# rrcmd.net
KiCad netlist of a schematic drawn in EAGLE
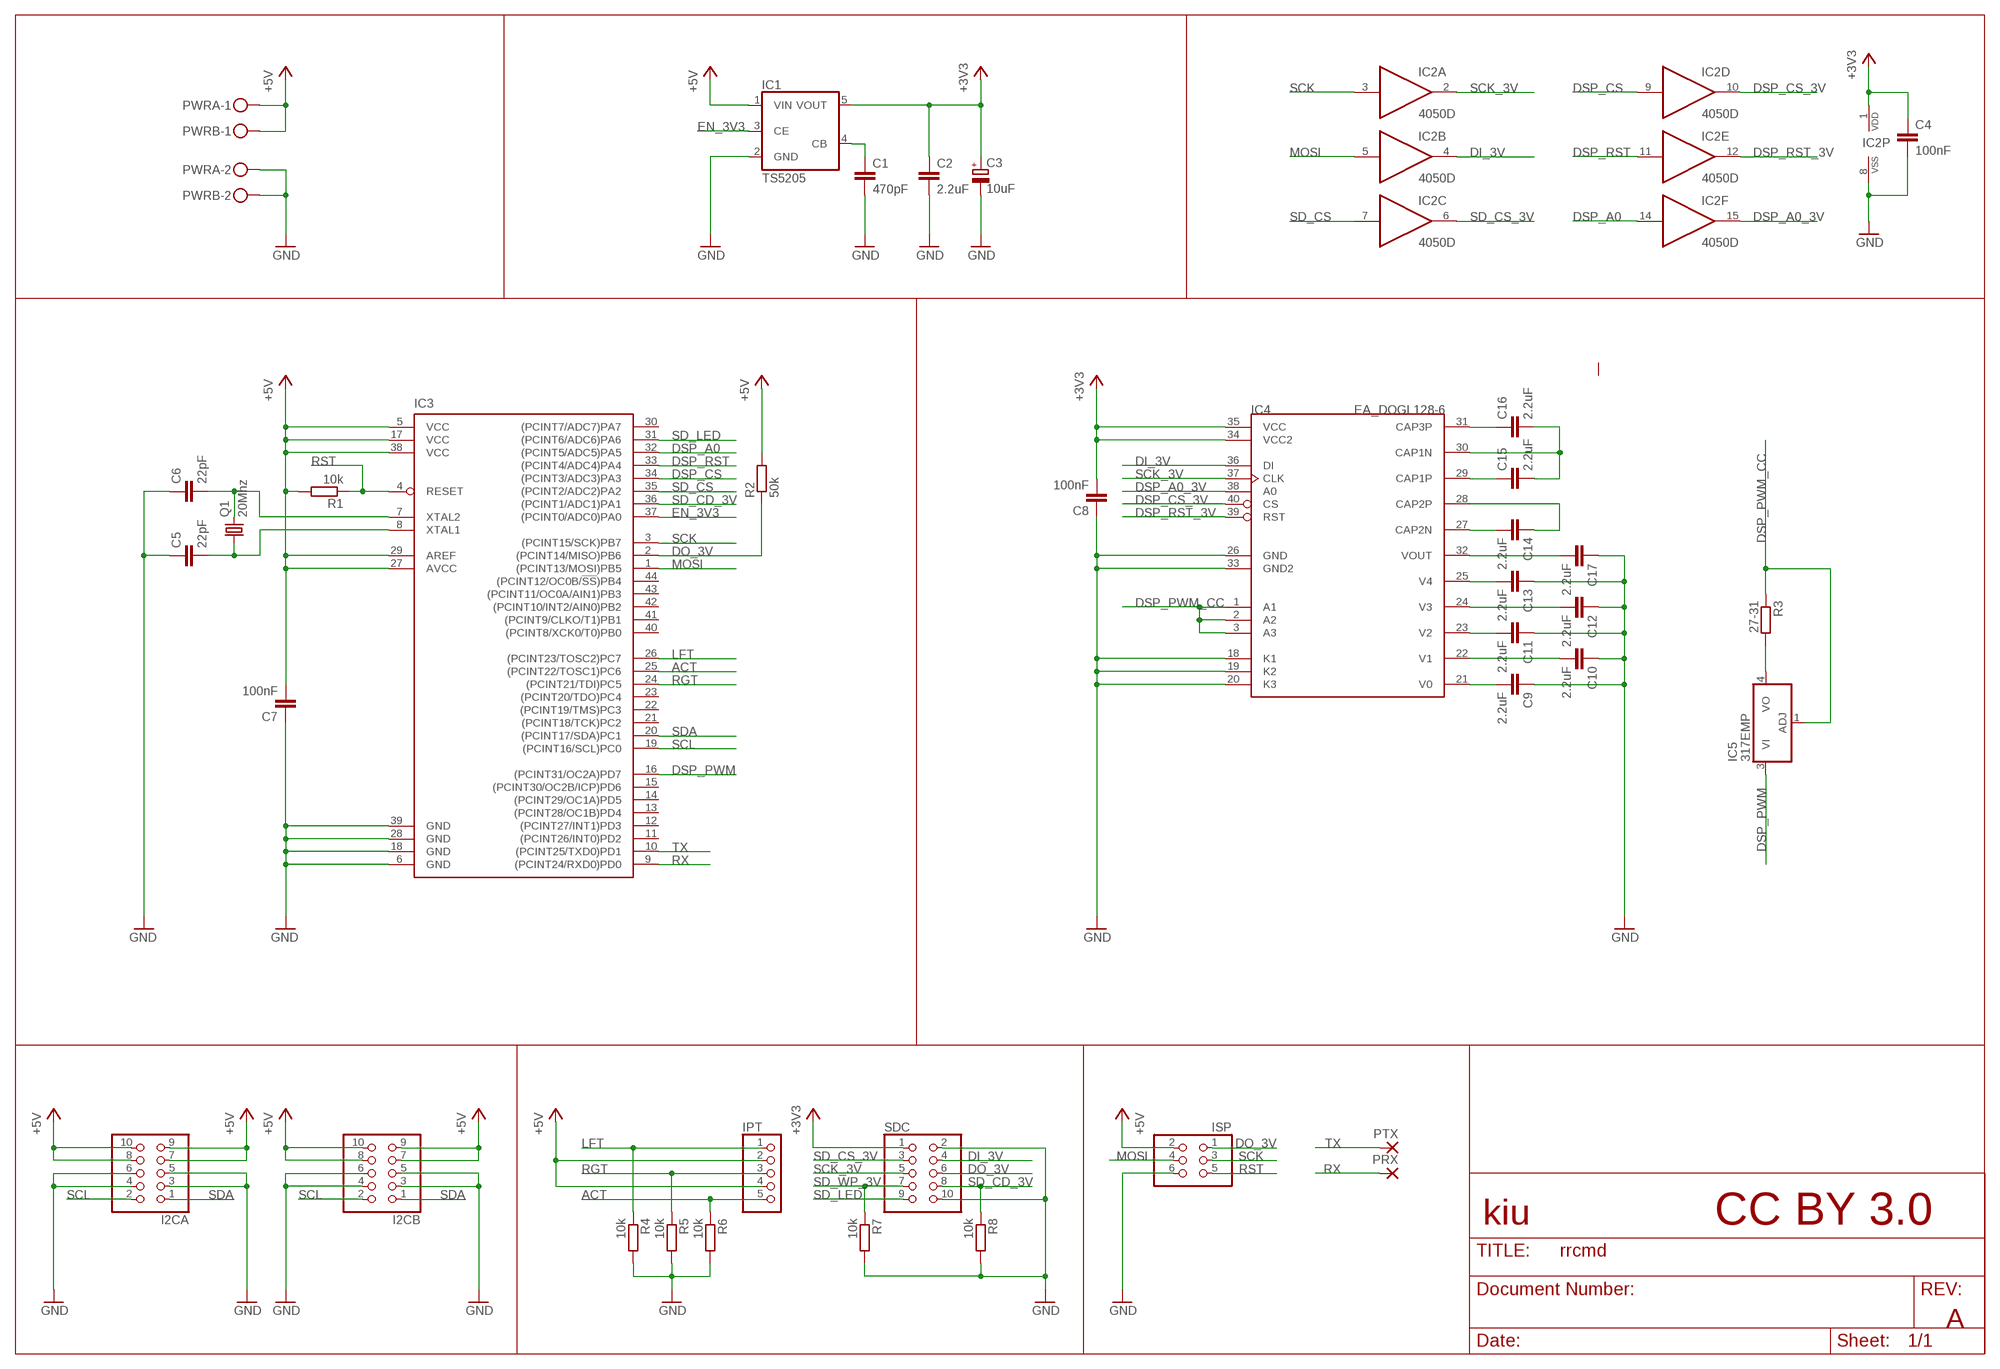
[diagram p0: schematic, sheet 1]

(export (version "E")
  (design (tool "Eeschema 10.0.6"))
  (components
    (comp (ref "C1")
      (value "470pF")
      (footprint "eagle-import:C0805")
      (libsource (lib "eagle-import") (part "C-EUC0805"))
    )
    (comp (ref "C2")
      (value "2.2uF")
      (footprint "eagle-import:C0805")
      (libsource (lib "eagle-import") (part "C-EUC0805"))
    )
    (comp (ref "C3")
      (value "10uF")
      (footprint "eagle-import:CT3216")
      (libsource (lib "eagle-import") (part "CPOL-EUCT3216"))
    )
    (comp (ref "C4")
      (value "100nF")
      (footprint "eagle-import:C0805")
      (libsource (lib "eagle-import") (part "C-EUC0805"))
    )
    (comp (ref "C5")
      (value "22pF")
      (footprint "eagle-import:C0805")
      (libsource (lib "eagle-import") (part "C-EUC0805"))
    )
    (comp (ref "C6")
      (value "22pF")
      (footprint "eagle-import:C0805")
      (libsource (lib "eagle-import") (part "C-EUC0805"))
    )
    (comp (ref "C7")
      (value "100nF")
      (footprint "eagle-import:C0805")
      (libsource (lib "eagle-import") (part "C-EUC0805"))
    )
    (comp (ref "C8")
      (value "100nF")
      (footprint "eagle-import:C0805")
      (libsource (lib "eagle-import") (part "C-EUC0805"))
    )
    (comp (ref "C9")
      (value "2.2uF")
      (footprint "eagle-import:C0805")
      (libsource (lib "eagle-import") (part "C-EUC0805"))
    )
    (comp (ref "C10")
      (value "2.2uF")
      (footprint "eagle-import:C0805")
      (libsource (lib "eagle-import") (part "C-EUC0805"))
    )
    (comp (ref "C11")
      (value "2.2uF")
      (footprint "eagle-import:C0805")
      (libsource (lib "eagle-import") (part "C-EUC0805"))
    )
    (comp (ref "C12")
      (value "2.2uF")
      (footprint "eagle-import:C0805")
      (libsource (lib "eagle-import") (part "C-EUC0805"))
    )
    (comp (ref "C13")
      (value "2.2uF")
      (footprint "eagle-import:C0805")
      (libsource (lib "eagle-import") (part "C-EUC0805"))
    )
    (comp (ref "C14")
      (value "2.2uF")
      (footprint "eagle-import:C0805")
      (libsource (lib "eagle-import") (part "C-EUC0805"))
    )
    (comp (ref "C15")
      (value "2.2uF")
      (footprint "eagle-import:C0805")
      (libsource (lib "eagle-import") (part "C-EUC0805"))
    )
    (comp (ref "C16")
      (value "2.2uF")
      (footprint "eagle-import:C0805")
      (libsource (lib "eagle-import") (part "C-EUC0805"))
    )
    (comp (ref "C17")
      (value "2.2uF")
      (footprint "eagle-import:C0805")
      (libsource (lib "eagle-import") (part "C-EUC0805"))
    )
    (comp (ref "I2CA")
      (value "PINHD-2X5")
      (footprint "eagle-import:2X05")
      (libsource (lib "eagle-import") (part "PINHD-2X5"))
    )
    (comp (ref "I2CB")
      (value "PINHD-2X5")
      (footprint "eagle-import:2X05")
      (libsource (lib "eagle-import") (part "PINHD-2X5"))
    )
    (comp (ref "IC1")
      (value "TS5205")
      (footprint "eagle-import:SOT25")
      (libsource (lib "eagle-import") (part "TS5205"))
    )
    (comp (ref "IC2")
      (value "4050D")
      (footprint "eagle-import:SO16")
      (libsource (lib "eagle-import") (part "4050D"))
    )
    (comp (ref "IC3")
      (value "ATMEGA644A")
      (footprint "eagle-import:TQFP44")
      (fields (field (name "MPN") "ATMEGA644PV-10AU"))
      (libsource (lib "eagle-import") (part "ATMEGA644A"))
    )
    (comp (ref "IC4")
      (value "EA_DOGL128-6")
      (footprint "eagle-import:EA_DOGL128-6")
      (libsource (lib "eagle-import") (part "EA_DOGL128-6"))
    )
    (comp (ref "IC5")
      (value "317EMP")
      (footprint "eagle-import:SOT223")
      (libsource (lib "eagle-import") (part "317EMP"))
    )
    (comp (ref "IPT")
      (value "PINHD-1X5")
      (footprint "eagle-import:1X05")
      (libsource (lib "eagle-import") (part "PINHD-1X5"))
    )
    (comp (ref "ISP")
      (value "PINHD-2X3")
      (footprint "eagle-import:2X03")
      (libsource (lib "eagle-import") (part "PINHD-2X3"))
    )
    (comp (ref "PRX")
      (value "SMD2")
      (footprint "eagle-import:SMD1,27-2,54")
      (libsource (lib "eagle-import") (part "SMD2"))
    )
    (comp (ref "PTX")
      (value "SMD2")
      (footprint "eagle-import:SMD1,27-2,54")
      (libsource (lib "eagle-import") (part "SMD2"))
    )
    (comp (ref "PWRA")
      (value "MKDSN1,5/2-5,08")
      (footprint "eagle-import:MKDSN1,5_2-5,08")
      (fields (field (name "MPN") "MKDSN 1,5/2-5.08"))
      (libsource (lib "eagle-import") (part "MKDSN1,5/2-5,08"))
    )
    (comp (ref "PWRB")
      (value "MKDSN1,5/2-5,08")
      (footprint "eagle-import:MKDSN1,5_2-5,08")
      (fields (field (name "MPN") "MKDSN 1,5/2-5.08"))
      (libsource (lib "eagle-import") (part "MKDSN1,5/2-5,08"))
    )
    (comp (ref "Q1")
      (value "20Mhz")
      (footprint "eagle-import:HC49UP")
      (libsource (lib "eagle-import") (part "CRYSTALHC49UP"))
    )
    (comp (ref "R1")
      (value "10k")
      (footprint "eagle-import:R0805")
      (libsource (lib "eagle-import") (part "R-EU_R0805"))
    )
    (comp (ref "R2")
      (value "50k")
      (footprint "eagle-import:R0805")
      (libsource (lib "eagle-import") (part "R-EU_R0805"))
    )
    (comp (ref "R3")
      (value "27-31")
      (footprint "eagle-import:R0805")
      (libsource (lib "eagle-import") (part "R-EU_R0805"))
    )
    (comp (ref "R4")
      (value "10k")
      (footprint "eagle-import:R0805")
      (libsource (lib "eagle-import") (part "R-EU_R0805"))
    )
    (comp (ref "R5")
      (value "10k")
      (footprint "eagle-import:R0805")
      (libsource (lib "eagle-import") (part "R-EU_R0805"))
    )
    (comp (ref "R6")
      (value "10k")
      (footprint "eagle-import:R0805")
      (libsource (lib "eagle-import") (part "R-EU_R0805"))
    )
    (comp (ref "R7")
      (value "10k")
      (footprint "eagle-import:R0805")
      (libsource (lib "eagle-import") (part "R-EU_R0805"))
    )
    (comp (ref "R8")
      (value "10k")
      (footprint "eagle-import:R0805")
      (libsource (lib "eagle-import") (part "R-EU_R0805"))
    )
    (comp (ref "SDC")
      (value "PINHD-2X5")
      (footprint "eagle-import:2X05")
      (libsource (lib "eagle-import") (part "PINHD-2X5"))
    )
  )
  (nets
    (net (code "1") (name "+3V3") (class "Default")
      (node (ref "C2") (pin "1") (pinfunction "1_1") (pintype "passive"))
      (node (ref "C3") (pin "+") (pinfunction "+_+") (pintype "passive"))
      (node (ref "C4") (pin "1") (pinfunction "1_1") (pintype "passive"))
      (node (ref "C8") (pin "2") (pinfunction "2_2") (pintype "passive"))
      (node (ref "IC1") (pin "5") (pinfunction "VOUT_5") (pintype "passive"))
      (node (ref "IC2") (pin "1") (pinfunction "VDD_1") (pintype "power_in"))
      (node (ref "IC4") (pin "34") (pinfunction "VCC2_34") (pintype "power_in"))
      (node (ref "IC4") (pin "35") (pinfunction "VCC_35") (pintype "power_in"))
      (node (ref "SDC") (pin "1") (pinfunction "1_1") (pintype "passive"))
    )
    (net (code "2") (name "+5V") (class "Default")
      (node (ref "C7") (pin "2") (pinfunction "2_2") (pintype "passive"))
      (node (ref "I2CA") (pin "10") (pinfunction "10_10") (pintype "passive"))
      (node (ref "I2CA") (pin "7") (pinfunction "7_7") (pintype "passive"))
      (node (ref "I2CA") (pin "8") (pinfunction "8_8") (pintype "passive"))
      (node (ref "I2CA") (pin "9") (pinfunction "9_9") (pintype "passive"))
      (node (ref "I2CB") (pin "10") (pinfunction "10_10") (pintype "passive"))
      (node (ref "I2CB") (pin "7") (pinfunction "7_7") (pintype "passive"))
      (node (ref "I2CB") (pin "8") (pinfunction "8_8") (pintype "passive"))
      (node (ref "I2CB") (pin "9") (pinfunction "9_9") (pintype "passive"))
      (node (ref "IC1") (pin "1") (pinfunction "VIN_1") (pintype "input"))
      (node (ref "IC3") (pin "17") (pinfunction "VCC_17") (pintype "power_in"))
      (node (ref "IC3") (pin "27") (pinfunction "AVCC_27") (pintype "power_in"))
      (node (ref "IC3") (pin "29") (pinfunction "AREF_29") (pintype "passive"))
      (node (ref "IC3") (pin "38") (pinfunction "VCC_38") (pintype "power_in"))
      (node (ref "IC3") (pin "5") (pinfunction "VCC_5") (pintype "power_in"))
      (node (ref "IPT") (pin "2") (pinfunction "2_2") (pintype "passive"))
      (node (ref "IPT") (pin "4") (pinfunction "4_4") (pintype "passive"))
      (node (ref "ISP") (pin "2") (pinfunction "2_2") (pintype "passive"))
      (node (ref "PWRA") (pin "1") (pinfunction "KL_1") (pintype "passive"))
      (node (ref "PWRB") (pin "1") (pinfunction "KL_1") (pintype "passive"))
      (node (ref "R1") (pin "2") (pinfunction "2_2") (pintype "passive"))
      (node (ref "R2") (pin "2") (pinfunction "2_2") (pintype "passive"))
    )
    (net (code "3") (name "/ACT") (class "Default")
      (node (ref "IC3") (pin "25") (pinfunction "(PCINT22/TOSC1)PC6_25") (pintype "output"))
      (node (ref "IPT") (pin "5") (pinfunction "5_5") (pintype "passive"))
      (node (ref "R6") (pin "1") (pinfunction "1_1") (pintype "passive"))
    )
    (net (code "4") (name "/DI_3V") (class "Default")
      (node (ref "IC2") (pin "4") (pinfunction "O_4") (pintype "output"))
      (node (ref "IC4") (pin "36") (pinfunction "DI_36") (pintype "input"))
      (node (ref "SDC") (pin "4") (pinfunction "4_4") (pintype "passive"))
    )
    (net (code "5") (name "/DO_3V") (class "Default")
      (node (ref "IC3") (pin "2") (pinfunction "(PCINT14/MISO)PB6_2") (pintype "bidirectional"))
      (node (ref "ISP") (pin "1") (pinfunction "1_1") (pintype "passive"))
      (node (ref "R2") (pin "1") (pinfunction "1_1") (pintype "passive"))
      (node (ref "SDC") (pin "6") (pinfunction "6_6") (pintype "passive"))
    )
    (net (code "6") (name "/DSP_A0") (class "Default")
      (node (ref "IC2") (pin "14") (pinfunction "I_14") (pintype "input"))
      (node (ref "IC3") (pin "32") (pinfunction "(PCINT5/ADC5)PA5_32") (pintype "bidirectional"))
    )
    (net (code "7") (name "/DSP_A0_3V") (class "Default")
      (node (ref "IC2") (pin "15") (pinfunction "O_15") (pintype "output"))
      (node (ref "IC4") (pin "38") (pinfunction "A0_38") (pintype "input"))
    )
    (net (code "8") (name "/DSP_CS") (class "Default")
      (node (ref "IC2") (pin "9") (pinfunction "I_9") (pintype "input"))
      (node (ref "IC3") (pin "34") (pinfunction "(PCINT3/ADC3)PA3_34") (pintype "bidirectional"))
    )
    (net (code "9") (name "/DSP_CS_3V") (class "Default")
      (node (ref "IC2") (pin "10") (pinfunction "O_10") (pintype "output"))
      (node (ref "IC4") (pin "40") (pinfunction "CS_40") (pintype "input"))
    )
    (net (code "10") (name "/DSP_PWM") (class "Default")
      (node (ref "IC3") (pin "16") (pinfunction "(PCINT31/OC2A)PD7_16") (pintype "bidirectional"))
      (node (ref "IC5") (pin "3") (pinfunction "VI_3") (pintype "input"))
    )
    (net (code "11") (name "/DSP_PWM_CC") (class "Default")
      (node (ref "IC4") (pin "1") (pinfunction "A1_1") (pintype "power_in"))
      (node (ref "IC4") (pin "2") (pinfunction "A2_2") (pintype "power_in"))
      (node (ref "IC4") (pin "3") (pinfunction "A3_3") (pintype "power_in"))
      (node (ref "IC5") (pin "1") (pinfunction "ADJ_1") (pintype "input"))
      (node (ref "R3") (pin "1") (pinfunction "1_1") (pintype "passive"))
    )
    (net (code "12") (name "/DSP_RST") (class "Default")
      (node (ref "IC2") (pin "11") (pinfunction "I_11") (pintype "input"))
      (node (ref "IC3") (pin "33") (pinfunction "(PCINT4/ADC4)PA4_33") (pintype "bidirectional"))
    )
    (net (code "13") (name "/DSP_RST_3V") (class "Default")
      (node (ref "IC2") (pin "12") (pinfunction "O_12") (pintype "output"))
      (node (ref "IC4") (pin "39") (pinfunction "RST_39") (pintype "input"))
    )
    (net (code "14") (name "/EN_3V3") (class "Default")
      (node (ref "IC1") (pin "3") (pinfunction "CE_3") (pintype "input"))
      (node (ref "IC3") (pin "37") (pinfunction "(PCINT0/ADC0)PA0_37") (pintype "bidirectional"))
    )
    (net (code "15") (name "/LFT") (class "Default")
      (node (ref "IC3") (pin "26") (pinfunction "(PCINT23/TOSC2)PC7_26") (pintype "output"))
      (node (ref "IPT") (pin "1") (pinfunction "1_1") (pintype "passive"))
      (node (ref "R4") (pin "1") (pinfunction "1_1") (pintype "passive"))
    )
    (net (code "16") (name "/MOSI") (class "Default")
      (node (ref "IC2") (pin "5") (pinfunction "I_5") (pintype "input"))
      (node (ref "IC3") (pin "1") (pinfunction "(PCINT13/MOSI)PB5_1") (pintype "bidirectional"))
      (node (ref "ISP") (pin "4") (pinfunction "4_4") (pintype "passive"))
    )
    (net (code "17") (name "/RGT") (class "Default")
      (node (ref "IC3") (pin "24") (pinfunction "(PCINT21/TDI)PC5_24") (pintype "output"))
      (node (ref "IPT") (pin "3") (pinfunction "3_3") (pintype "passive"))
      (node (ref "R5") (pin "1") (pinfunction "1_1") (pintype "passive"))
    )
    (net (code "18") (name "/RST") (class "Default")
      (node (ref "IC3") (pin "4") (pinfunction "RESET_4") (pintype "input"))
      (node (ref "ISP") (pin "5") (pinfunction "5_5") (pintype "passive"))
      (node (ref "R1") (pin "1") (pinfunction "1_1") (pintype "passive"))
    )
    (net (code "19") (name "/RX") (class "Default")
      (node (ref "IC3") (pin "9") (pinfunction "(PCINT24/RXD0)PD0_9") (pintype "bidirectional"))
      (node (ref "PRX") (pin "1") (pinfunction "P_1") (pintype "passive"))
    )
    (net (code "20") (name "/SCK") (class "Default")
      (node (ref "IC2") (pin "3") (pinfunction "I_3") (pintype "input"))
      (node (ref "IC3") (pin "3") (pinfunction "(PCINT15/SCK)PB7_3") (pintype "bidirectional"))
      (node (ref "ISP") (pin "3") (pinfunction "3_3") (pintype "passive"))
    )
    (net (code "21") (name "/SCK_3V") (class "Default")
      (node (ref "IC2") (pin "2") (pinfunction "O_2") (pintype "output"))
      (node (ref "IC4") (pin "37") (pinfunction "CLK_37") (pintype "input"))
      (node (ref "SDC") (pin "5") (pinfunction "5_5") (pintype "passive"))
    )
    (net (code "22") (name "/SCL") (class "Default")
      (node (ref "I2CA") (pin "2") (pinfunction "2_2") (pintype "passive"))
      (node (ref "I2CB") (pin "2") (pinfunction "2_2") (pintype "passive"))
      (node (ref "IC3") (pin "19") (pinfunction "(PCINT16/SCL)PC0_19") (pintype "output"))
    )
    (net (code "23") (name "/SDA") (class "Default")
      (node (ref "I2CA") (pin "1") (pinfunction "1_1") (pintype "passive"))
      (node (ref "I2CB") (pin "1") (pinfunction "1_1") (pintype "passive"))
      (node (ref "IC3") (pin "20") (pinfunction "(PCINT17/SDA)PC1_20") (pintype "output"))
    )
    (net (code "24") (name "/SD_CD_3V") (class "Default")
      (node (ref "IC3") (pin "36") (pinfunction "(PCINT1/ADC1)PA1_36") (pintype "bidirectional"))
      (node (ref "R8") (pin "1") (pinfunction "1_1") (pintype "passive"))
      (node (ref "SDC") (pin "8") (pinfunction "8_8") (pintype "passive"))
    )
    (net (code "25") (name "/SD_CS") (class "Default")
      (node (ref "IC2") (pin "7") (pinfunction "I_7") (pintype "input"))
      (node (ref "IC3") (pin "35") (pinfunction "(PCINT2/ADC2)PA2_35") (pintype "bidirectional"))
    )
    (net (code "26") (name "/SD_CS_3V") (class "Default")
      (node (ref "IC2") (pin "6") (pinfunction "O_6") (pintype "output"))
      (node (ref "SDC") (pin "3") (pinfunction "3_3") (pintype "passive"))
    )
    (net (code "27") (name "/SD_LED") (class "Default")
      (node (ref "IC3") (pin "31") (pinfunction "(PCINT6/ADC6)PA6_31") (pintype "bidirectional"))
      (node (ref "SDC") (pin "9") (pinfunction "9_9") (pintype "passive"))
    )
    (net (code "28") (name "/SD_WP_3V") (class "Default")
      (node (ref "R7") (pin "1") (pinfunction "1_1") (pintype "passive"))
      (node (ref "SDC") (pin "7") (pinfunction "7_7") (pintype "passive"))
    )
    (net (code "29") (name "/TX") (class "Default")
      (node (ref "IC3") (pin "10") (pinfunction "(PCINT25/TXD0)PD1_10") (pintype "bidirectional"))
      (node (ref "PTX") (pin "1") (pinfunction "P_1") (pintype "passive"))
    )
    (net (code "30") (name "GND") (class "Default")
      (node (ref "C1") (pin "2") (pinfunction "2_2") (pintype "passive"))
      (node (ref "C10") (pin "1") (pinfunction "1_1") (pintype "passive"))
      (node (ref "C11") (pin "1") (pinfunction "1_1") (pintype "passive"))
      (node (ref "C12") (pin "1") (pinfunction "1_1") (pintype "passive"))
      (node (ref "C13") (pin "1") (pinfunction "1_1") (pintype "passive"))
      (node (ref "C17") (pin "1") (pinfunction "1_1") (pintype "passive"))
      (node (ref "C2") (pin "2") (pinfunction "2_2") (pintype "passive"))
      (node (ref "C3") (pin "-") (pinfunction "-_-") (pintype "passive"))
      (node (ref "C4") (pin "2") (pinfunction "2_2") (pintype "passive"))
      (node (ref "C5") (pin "1") (pinfunction "1_1") (pintype "passive"))
      (node (ref "C6") (pin "1") (pinfunction "1_1") (pintype "passive"))
      (node (ref "C7") (pin "1") (pinfunction "1_1") (pintype "passive"))
      (node (ref "C8") (pin "1") (pinfunction "1_1") (pintype "passive"))
      (node (ref "C9") (pin "1") (pinfunction "1_1") (pintype "passive"))
      (node (ref "I2CA") (pin "3") (pinfunction "3_3") (pintype "passive"))
      (node (ref "I2CA") (pin "4") (pinfunction "4_4") (pintype "passive"))
      (node (ref "I2CA") (pin "5") (pinfunction "5_5") (pintype "passive"))
      (node (ref "I2CA") (pin "6") (pinfunction "6_6") (pintype "passive"))
      (node (ref "I2CB") (pin "3") (pinfunction "3_3") (pintype "passive"))
      (node (ref "I2CB") (pin "4") (pinfunction "4_4") (pintype "passive"))
      (node (ref "I2CB") (pin "5") (pinfunction "5_5") (pintype "passive"))
      (node (ref "I2CB") (pin "6") (pinfunction "6_6") (pintype "passive"))
      (node (ref "IC1") (pin "2") (pinfunction "GND_2") (pintype "passive"))
      (node (ref "IC2") (pin "8") (pinfunction "VSS_8") (pintype "power_in"))
      (node (ref "IC3") (pin "18") (pinfunction "GND_18") (pintype "power_in"))
      (node (ref "IC3") (pin "28") (pinfunction "GND_28") (pintype "power_in"))
      (node (ref "IC3") (pin "39") (pinfunction "GND_39") (pintype "power_in"))
      (node (ref "IC3") (pin "6") (pinfunction "GND_6") (pintype "power_in"))
      (node (ref "IC4") (pin "18") (pinfunction "K1_18") (pintype "power_in"))
      (node (ref "IC4") (pin "19") (pinfunction "K2_19") (pintype "power_in"))
      (node (ref "IC4") (pin "20") (pinfunction "K3_20") (pintype "power_in"))
      (node (ref "IC4") (pin "26") (pinfunction "GND_26") (pintype "power_in"))
      (node (ref "IC4") (pin "33") (pinfunction "GND2_33") (pintype "power_in"))
      (node (ref "ISP") (pin "6") (pinfunction "6_6") (pintype "passive"))
      (node (ref "PWRA") (pin "2") (pinfunction "KL_2") (pintype "passive"))
      (node (ref "PWRB") (pin "2") (pinfunction "KL_2") (pintype "passive"))
      (node (ref "R4") (pin "2") (pinfunction "2_2") (pintype "passive"))
      (node (ref "R5") (pin "2") (pinfunction "2_2") (pintype "passive"))
      (node (ref "R6") (pin "2") (pinfunction "2_2") (pintype "passive"))
      (node (ref "R7") (pin "2") (pinfunction "2_2") (pintype "passive"))
      (node (ref "R8") (pin "2") (pinfunction "2_2") (pintype "passive"))
      (node (ref "SDC") (pin "10") (pinfunction "10_10") (pintype "passive"))
      (node (ref "SDC") (pin "2") (pinfunction "2_2") (pintype "passive"))
    )
    (net (code "31") (name "Net-(IC1-CB)") (class "Default")
      (node (ref "C1") (pin "1") (pinfunction "1_1") (pintype "passive"))
      (node (ref "IC1") (pin "4") (pinfunction "CB_4") (pintype "input"))
    )
    (net (code "32") (name "Net-(IC3-XTAL1)") (class "Default")
      (node (ref "C5") (pin "2") (pinfunction "2_2") (pintype "passive"))
      (node (ref "IC3") (pin "8") (pinfunction "XTAL1_8") (pintype "bidirectional"))
      (node (ref "Q1") (pin "1") (pinfunction "1_1") (pintype "passive"))
    )
    (net (code "33") (name "Net-(IC3-XTAL2)") (class "Default")
      (node (ref "C6") (pin "2") (pinfunction "2_2") (pintype "passive"))
      (node (ref "IC3") (pin "7") (pinfunction "XTAL2_7") (pintype "bidirectional"))
      (node (ref "Q1") (pin "2") (pinfunction "2_2") (pintype "passive"))
    )
    (net (code "34") (name "Net-(IC4-CAP1N)") (class "Default")
      (node (ref "C15") (pin "2") (pinfunction "2_2") (pintype "passive"))
      (node (ref "C16") (pin "2") (pinfunction "2_2") (pintype "passive"))
      (node (ref "IC4") (pin "30") (pinfunction "CAP1N_30") (pintype "power_in"))
    )
    (net (code "35") (name "Net-(IC4-CAP1P)") (class "Default")
      (node (ref "C15") (pin "1") (pinfunction "1_1") (pintype "passive"))
      (node (ref "IC4") (pin "29") (pinfunction "CAP1P_29") (pintype "power_in"))
    )
    (net (code "36") (name "Net-(IC4-CAP2N)") (class "Default")
      (node (ref "C14") (pin "2") (pinfunction "2_2") (pintype "passive"))
      (node (ref "IC4") (pin "27") (pinfunction "CAP2N_27") (pintype "power_in"))
    )
    (net (code "37") (name "Net-(IC4-CAP2P)") (class "Default")
      (node (ref "C14") (pin "1") (pinfunction "1_1") (pintype "passive"))
      (node (ref "IC4") (pin "28") (pinfunction "CAP2P_28") (pintype "power_in"))
    )
    (net (code "38") (name "Net-(IC4-CAP3P)") (class "Default")
      (node (ref "C16") (pin "1") (pinfunction "1_1") (pintype "passive"))
      (node (ref "IC4") (pin "31") (pinfunction "CAP3P_31") (pintype "power_in"))
    )
    (net (code "39") (name "Net-(IC4-V0)") (class "Default")
      (node (ref "C9") (pin "2") (pinfunction "2_2") (pintype "passive"))
      (node (ref "IC4") (pin "21") (pinfunction "V0_21") (pintype "power_in"))
    )
    (net (code "40") (name "Net-(IC4-V1)") (class "Default")
      (node (ref "C10") (pin "2") (pinfunction "2_2") (pintype "passive"))
      (node (ref "IC4") (pin "22") (pinfunction "V1_22") (pintype "power_in"))
    )
    (net (code "41") (name "Net-(IC4-V2)") (class "Default")
      (node (ref "C11") (pin "2") (pinfunction "2_2") (pintype "passive"))
      (node (ref "IC4") (pin "23") (pinfunction "V2_23") (pintype "power_in"))
    )
    (net (code "42") (name "Net-(IC4-V3)") (class "Default")
      (node (ref "C12") (pin "2") (pinfunction "2_2") (pintype "passive"))
      (node (ref "IC4") (pin "24") (pinfunction "V3_24") (pintype "power_in"))
    )
    (net (code "43") (name "Net-(IC4-V4)") (class "Default")
      (node (ref "C13") (pin "2") (pinfunction "2_2") (pintype "passive"))
      (node (ref "IC4") (pin "25") (pinfunction "V4_25") (pintype "power_in"))
    )
    (net (code "44") (name "Net-(IC4-VOUT)") (class "Default")
      (node (ref "C17") (pin "2") (pinfunction "2_2") (pintype "passive"))
      (node (ref "IC4") (pin "32") (pinfunction "VOUT_32") (pintype "power_in"))
    )
    (net (code "45") (name "Net-(IC5-VO)") (class "Default")
      (node (ref "IC5") (pin "4") (pinfunction "VO_4") (pintype "passive"))
      (node (ref "R3") (pin "2") (pinfunction "2_2") (pintype "passive"))
    )
    (net (code "46") (name "unconnected-(IC3-(PCINT7{slash}ADC7)PA7-Pad30)") (class "Default")
      (node (ref "IC3") (pin "30") (pinfunction "(PCINT7/ADC7)PA7_30") (pintype "bidirectional"))
    )
    (net (code "47") (name "unconnected-(IC3-(PCINT8{slash}XCK0{slash}T0)PB0-Pad40)") (class "Default")
      (node (ref "IC3") (pin "40") (pinfunction "(PCINT8/XCK0/T0)PB0_40") (pintype "bidirectional"))
    )
    (net (code "48") (name "unconnected-(IC3-(PCINT9{slash}CLKO{slash}T1)PB1-Pad41)") (class "Default")
      (node (ref "IC3") (pin "41") (pinfunction "(PCINT9/CLKO/T1)PB1_41") (pintype "bidirectional"))
    )
    (net (code "49") (name "unconnected-(IC3-(PCINT10{slash}INT2{slash}AIN0)PB2-Pad42)") (class "Default")
      (node (ref "IC3") (pin "42") (pinfunction "(PCINT10/INT2/AIN0)PB2_42") (pintype "bidirectional"))
    )
    (net (code "50") (name "unconnected-(IC3-(PCINT11{slash}OC0A{slash}AIN1)PB3-Pad43)") (class "Default")
      (node (ref "IC3") (pin "43") (pinfunction "(PCINT11/OC0A/AIN1)PB3_43") (pintype "bidirectional"))
    )
    (net (code "51") (name "unconnected-(IC3-(PCINT12{slash}OC0B{slash}~{SS})PB4-Pad44)") (class "Default")
      (node (ref "IC3") (pin "44") (pinfunction "(PCINT12/OC0B/~{SS})PB4_44") (pintype "bidirectional"))
    )
    (net (code "52") (name "unconnected-(IC3-(PCINT18{slash}TCK)PC2-Pad21)") (class "Default")
      (node (ref "IC3") (pin "21") (pinfunction "(PCINT18/TCK)PC2_21") (pintype "output"))
    )
    (net (code "53") (name "unconnected-(IC3-(PCINT19{slash}TMS)PC3-Pad22)") (class "Default")
      (node (ref "IC3") (pin "22") (pinfunction "(PCINT19/TMS)PC3_22") (pintype "output"))
    )
    (net (code "54") (name "unconnected-(IC3-(PCINT20{slash}TDO)PC4-Pad23)") (class "Default")
      (node (ref "IC3") (pin "23") (pinfunction "(PCINT20/TDO)PC4_23") (pintype "output"))
    )
    (net (code "55") (name "unconnected-(IC3-(PCINT26{slash}INT0)PD2-Pad11)") (class "Default")
      (node (ref "IC3") (pin "11") (pinfunction "(PCINT26/INT0)PD2_11") (pintype "bidirectional"))
    )
    (net (code "56") (name "unconnected-(IC3-(PCINT27{slash}INT1)PD3-Pad12)") (class "Default")
      (node (ref "IC3") (pin "12") (pinfunction "(PCINT27/INT1)PD3_12") (pintype "bidirectional"))
    )
    (net (code "57") (name "unconnected-(IC3-(PCINT28{slash}OC1B)PD4-Pad13)") (class "Default")
      (node (ref "IC3") (pin "13") (pinfunction "(PCINT28/OC1B)PD4_13") (pintype "bidirectional"))
    )
    (net (code "58") (name "unconnected-(IC3-(PCINT29{slash}OC1A)PD5-Pad14)") (class "Default")
      (node (ref "IC3") (pin "14") (pinfunction "(PCINT29/OC1A)PD5_14") (pintype "bidirectional"))
    )
    (net (code "59") (name "unconnected-(IC3-(PCINT30{slash}OC2B{slash}ICP)PD6-Pad15)") (class "Default")
      (node (ref "IC3") (pin "15") (pinfunction "(PCINT30/OC2B/ICP)PD6_15") (pintype "bidirectional"))
    )
  )
)
